# Inputs1.net
KiCad netlist of a schematic drawn in Altium Designer
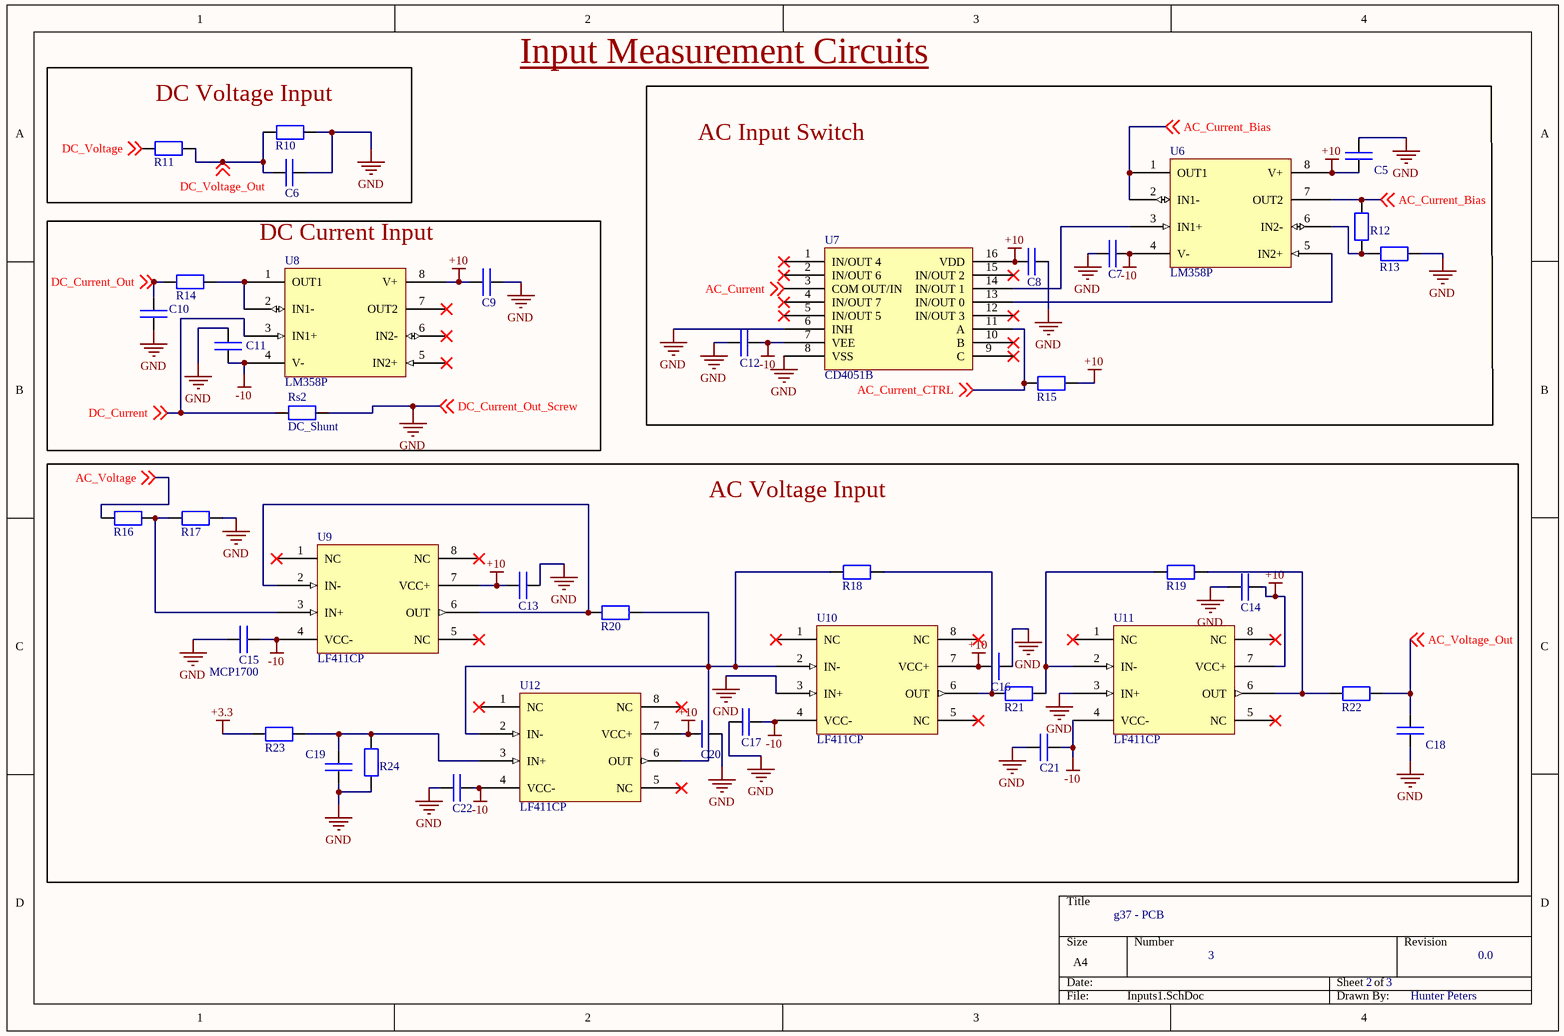
[diagram p0: Inputs1.SchDoc]

(export (version "E")
  (design (tool "Eeschema 10.0.6"))
  (components
    (comp (ref "C5")
      (value "Capacitor")
      (footprint "Capacitor")
      (libsource (lib "Schlib1") (part "Capacitor"))
    )
    (comp (ref "C6")
      (value "Capacitor")
      (footprint "Capacitor")
      (libsource (lib "Schlib1") (part "Capacitor"))
    )
    (comp (ref "C7")
      (value "Capacitor")
      (footprint "Capacitor")
      (libsource (lib "Schlib1") (part "Capacitor"))
    )
    (comp (ref "C8")
      (value "Capacitor")
      (footprint "Capacitor")
      (libsource (lib "Schlib1") (part "Capacitor"))
    )
    (comp (ref "C9")
      (value "Capacitor")
      (footprint "Capacitor")
      (libsource (lib "Schlib1") (part "Capacitor"))
    )
    (comp (ref "C10")
      (value "Capacitor")
      (footprint "Capacitor")
      (libsource (lib "Schlib1") (part "Capacitor"))
    )
    (comp (ref "C11")
      (value "Capacitor")
      (footprint "Capacitor")
      (libsource (lib "Schlib1") (part "Capacitor"))
    )
    (comp (ref "C12")
      (value "Capacitor")
      (footprint "Capacitor")
      (libsource (lib "Schlib1") (part "Capacitor"))
    )
    (comp (ref "C13")
      (value "Capacitor")
      (footprint "Capacitor")
      (libsource (lib "Schlib1") (part "Capacitor"))
    )
    (comp (ref "C14")
      (value "Capacitor")
      (footprint "Capacitor")
      (libsource (lib "Schlib1") (part "Capacitor"))
    )
    (comp (ref "C15")
      (value "Capacitor")
      (footprint "Capacitor")
      (libsource (lib "Schlib1") (part "Capacitor"))
    )
    (comp (ref "C16")
      (value "Capacitor")
      (footprint "Capacitor")
      (libsource (lib "Schlib1") (part "Capacitor"))
    )
    (comp (ref "C17")
      (value "Capacitor")
      (footprint "Capacitor")
      (libsource (lib "Schlib1") (part "Capacitor"))
    )
    (comp (ref "C18")
      (value "Capacitor")
      (footprint "Capacitor")
      (libsource (lib "Schlib1") (part "Capacitor"))
    )
    (comp (ref "C19")
      (value "Capacitor")
      (footprint "Capacitor")
      (libsource (lib "Schlib1") (part "Capacitor"))
    )
    (comp (ref "C20")
      (value "Capacitor")
      (footprint "Capacitor")
      (libsource (lib "Schlib1") (part "Capacitor"))
    )
    (comp (ref "C21")
      (value "Capacitor")
      (footprint "Capacitor")
      (libsource (lib "Schlib1") (part "Capacitor"))
    )
    (comp (ref "C22")
      (value "Capacitor")
      (footprint "Capacitor")
      (libsource (lib "Schlib1") (part "Capacitor"))
    )
    (comp (ref "R10") (value "Resistor") (footprint "Resistor") (libsource (lib "Schlib1") (part "Resistor")))
    (comp (ref "R11") (value "Resistor") (footprint "Resistor") (libsource (lib "Schlib1") (part "Resistor")))
    (comp (ref "R12") (value "Resistor") (footprint "Resistor") (libsource (lib "Schlib1") (part "Resistor")))
    (comp (ref "R13") (value "Resistor") (footprint "Resistor") (libsource (lib "Schlib1") (part "Resistor")))
    (comp (ref "R14") (value "Resistor") (footprint "Resistor") (libsource (lib "Schlib1") (part "Resistor")))
    (comp (ref "R15") (value "4.7kΩ") (footprint "Resistor") (libsource (lib "Schlib1") (part "Resistor")))
    (comp (ref "R16") (value "Resistor") (footprint "Resistor") (libsource (lib "Schlib1") (part "Resistor")))
    (comp (ref "R17") (value "Resistor") (footprint "Resistor") (libsource (lib "Schlib1") (part "Resistor")))
    (comp (ref "R18") (value "Resistor") (footprint "Resistor") (libsource (lib "Schlib1") (part "Resistor")))
    (comp (ref "R19") (value "Resistor") (footprint "Resistor") (libsource (lib "Schlib1") (part "Resistor")))
    (comp (ref "R20") (value "Resistor") (footprint "Resistor") (libsource (lib "Schlib1") (part "Resistor")))
    (comp (ref "R21") (value "Resistor") (footprint "Resistor") (libsource (lib "Schlib1") (part "Resistor")))
    (comp (ref "R22") (value "Resistor") (footprint "Resistor") (libsource (lib "Schlib1") (part "Resistor")))
    (comp (ref "R23") (value "Resistor") (footprint "Resistor") (libsource (lib "Schlib1") (part "Resistor")))
    (comp (ref "R24") (value "Resistor") (footprint "Resistor") (libsource (lib "Schlib1") (part "Resistor")))
    (comp (ref "Rs2") (value "DC_Shunt") (footprint "DC_Shunt") (libsource (lib "Schlib1") (part "DC_Shunt")))
    (comp (ref "U6")
      (value "LM358P")
      (footprint "Op Amp")
      (description "Operational Amplifier, Dual, 700 Khz, 2, 0.4 V/ S, 1.5V To 16V, Dip, 8 Rohs Compliant: Yes")
      (fields (field (name "MANUFACTURER") "Texas Instruments"))
      (libsource (lib "Schlib1") (part "LM358P"))
    )
    (comp (ref "U7")
      (value "CD4051B")
      (footprint "Multiplexor")
      (description "CD4051B Series 20 V 100 nA CMOS Single 8-Channel Analog Multiplexer - PDIP-16")
      (fields
        (field (name "MANUFACTURER") "Texas Instruments")
        (field (name "MANUFACTURER PART NUMBER") "CD4051BE")
      )
      (libsource (lib "Schlib1") (part "CD4051BE"))
    )
    (comp (ref "U8")
      (value "LM358P")
      (footprint "Op Amp")
      (description "Operational Amplifier, Dual, 700 Khz, 2, 0.4 V/ S, 1.5V To 16V, Dip, 8 Rohs Compliant: Yes")
      (fields (field (name "MANUFACTURER") "Texas Instruments"))
      (libsource (lib "Schlib1") (part "LM358P"))
    )
    (comp (ref "U9")
      (value "LF411CP")
      (footprint "Op Amp")
      (description "Operational Amplifier, 1 Func, 2000uV Offset-Max, JFET, PDIP8")
      (fields (field (name "MANUFACTURER") "Texas Instruments"))
      (libsource (lib "Schlib1") (part "LF411CP"))
    )
    (comp (ref "U10")
      (value "LF411CP")
      (footprint "Op Amp")
      (description "Operational Amplifier, 1 Func, 2000uV Offset-Max, JFET, PDIP8")
      (fields (field (name "MANUFACTURER") "Texas Instruments"))
      (libsource (lib "Schlib1") (part "LF411CP"))
    )
    (comp (ref "U11")
      (value "LF411CP")
      (footprint "Op Amp")
      (description "Operational Amplifier, 1 Func, 2000uV Offset-Max, JFET, PDIP8")
      (fields (field (name "MANUFACTURER") "Texas Instruments"))
      (libsource (lib "Schlib1") (part "LF411CP"))
    )
    (comp (ref "U12")
      (value "LF411CP")
      (footprint "Op Amp")
      (description "Operational Amplifier, 1 Func, 2000uV Offset-Max, JFET, PDIP8")
      (fields (field (name "MANUFACTURER") "Texas Instruments"))
      (libsource (lib "Schlib1") (part "LF411CP"))
    )
  )
  (nets
    (net (code "1") (name "+3.3") (class "Default")
      (node (ref "R23") (pin "1") (pinfunction "1_1") (pintype "passive"))
    )
    (net (code "2") (name "+10") (class "Default")
      (node (ref "C13") (pin "1") (pinfunction "1_1") (pintype "passive"))
      (node (ref "C14") (pin "1") (pinfunction "1_1") (pintype "passive"))
      (node (ref "C16") (pin "1") (pinfunction "1_1") (pintype "passive"))
      (node (ref "C20") (pin "1") (pinfunction "1_1") (pintype "passive"))
      (node (ref "C5") (pin "1") (pinfunction "1_1") (pintype "passive"))
      (node (ref "C8") (pin "1") (pinfunction "1_1") (pintype "passive"))
      (node (ref "C9") (pin "1") (pinfunction "1_1") (pintype "passive"))
      (node (ref "R15") (pin "2") (pinfunction "2_2") (pintype "passive"))
      (node (ref "U10") (pin "7") (pinfunction "VCC+_7") (pintype "power_in"))
      (node (ref "U11") (pin "7") (pinfunction "VCC+_7") (pintype "power_in"))
      (node (ref "U12") (pin "7") (pinfunction "VCC+_7") (pintype "power_in"))
      (node (ref "U6") (pin "8") (pinfunction "V+_8") (pintype "passive"))
      (node (ref "U7") (pin "16") (pinfunction "VDD_16") (pintype "passive"))
      (node (ref "U8") (pin "8") (pinfunction "V+_8") (pintype "passive"))
      (node (ref "U9") (pin "7") (pinfunction "VCC+_7") (pintype "power_in"))
    )
    (net (code "3") (name "-10") (class "Default")
      (node (ref "C11") (pin "1") (pinfunction "1_1") (pintype "passive"))
      (node (ref "C12") (pin "2") (pinfunction "2_2") (pintype "passive"))
      (node (ref "C15") (pin "2") (pinfunction "2_2") (pintype "passive"))
      (node (ref "C17") (pin "2") (pinfunction "2_2") (pintype "passive"))
      (node (ref "C21") (pin "2") (pinfunction "2_2") (pintype "passive"))
      (node (ref "C22") (pin "2") (pinfunction "2_2") (pintype "passive"))
      (node (ref "C7") (pin "2") (pinfunction "2_2") (pintype "passive"))
      (node (ref "U10") (pin "4") (pinfunction "VCC-_4") (pintype "power_in"))
      (node (ref "U11") (pin "4") (pinfunction "VCC-_4") (pintype "power_in"))
      (node (ref "U12") (pin "4") (pinfunction "VCC-_4") (pintype "power_in"))
      (node (ref "U6") (pin "4") (pinfunction "V-_4") (pintype "power_in"))
      (node (ref "U7") (pin "7") (pinfunction "VEE_7") (pintype "passive"))
      (node (ref "U8") (pin "4") (pinfunction "V-_4") (pintype "power_in"))
      (node (ref "U9") (pin "4") (pinfunction "VCC-_4") (pintype "power_in"))
    )
    (net (code "4") (name "AC_Current") (class "Default")
      (node (ref "U7") (pin "3") (pinfunction "COM_OUT/IN_3") (pintype "passive"))
    )
    (net (code "5") (name "AC_Current_Bias") (class "Default")
      (node (ref "R12") (pin "2") (pinfunction "2_2") (pintype "passive"))
      (node (ref "U6") (pin "1") (pinfunction "OUT1_1") (pintype "passive"))
      (node (ref "U6") (pin "2") (pinfunction "IN1-_2") (pintype "bidirectional"))
      (node (ref "U6") (pin "7") (pinfunction "OUT2_7") (pintype "passive"))
    )
    (net (code "6") (name "AC_Current_CTRL") (class "Default")
      (node (ref "R15") (pin "1") (pinfunction "1_1") (pintype "passive"))
      (node (ref "U7") (pin "11") (pinfunction "A_11") (pintype "passive"))
    )
    (net (code "7") (name "AC_Voltage") (class "Default")
      (node (ref "R16") (pin "1") (pinfunction "1_1") (pintype "passive"))
    )
    (net (code "8") (name "AC_Voltage_Out") (class "Default")
      (node (ref "C18") (pin "2") (pinfunction "2_2") (pintype "passive"))
      (node (ref "R22") (pin "2") (pinfunction "2_2") (pintype "passive"))
    )
    (net (code "9") (name "DC_Current") (class "Default")
      (node (ref "Rs2") (pin "1") (pinfunction "1_1") (pintype "passive"))
      (node (ref "U8") (pin "3") (pinfunction "IN1+_3") (pintype "input"))
    )
    (net (code "10") (name "DC_Current_Out") (class "Default")
      (node (ref "C10") (pin "2") (pinfunction "2_2") (pintype "passive"))
      (node (ref "R14") (pin "1") (pinfunction "1_1") (pintype "passive"))
    )
    (net (code "11") (name "DC_Current_Out_Screw") (class "Default")
      (node (ref "C10") (pin "1") (pinfunction "1_1") (pintype "passive"))
      (node (ref "C11") (pin "2") (pinfunction "2_2") (pintype "passive"))
      (node (ref "C12") (pin "1") (pinfunction "1_1") (pintype "passive"))
      (node (ref "C13") (pin "2") (pinfunction "2_2") (pintype "passive"))
      (node (ref "C14") (pin "2") (pinfunction "2_2") (pintype "passive"))
      (node (ref "C15") (pin "1") (pinfunction "1_1") (pintype "passive"))
      (node (ref "C16") (pin "2") (pinfunction "2_2") (pintype "passive"))
      (node (ref "C17") (pin "1") (pinfunction "1_1") (pintype "passive"))
      (node (ref "C18") (pin "1") (pinfunction "1_1") (pintype "passive"))
      (node (ref "C19") (pin "1") (pinfunction "1_1") (pintype "passive"))
      (node (ref "C20") (pin "2") (pinfunction "2_2") (pintype "passive"))
      (node (ref "C21") (pin "1") (pinfunction "1_1") (pintype "passive"))
      (node (ref "C22") (pin "1") (pinfunction "1_1") (pintype "passive"))
      (node (ref "C5") (pin "2") (pinfunction "2_2") (pintype "passive"))
      (node (ref "C6") (pin "2") (pinfunction "2_2") (pintype "passive"))
      (node (ref "C7") (pin "1") (pinfunction "1_1") (pintype "passive"))
      (node (ref "C8") (pin "2") (pinfunction "2_2") (pintype "passive"))
      (node (ref "C9") (pin "2") (pinfunction "2_2") (pintype "passive"))
      (node (ref "R10") (pin "2") (pinfunction "2_2") (pintype "passive"))
      (node (ref "R13") (pin "1") (pinfunction "1_1") (pintype "passive"))
      (node (ref "R17") (pin "2") (pinfunction "2_2") (pintype "passive"))
      (node (ref "R24") (pin "1") (pinfunction "1_1") (pintype "passive"))
      (node (ref "Rs2") (pin "2") (pinfunction "2_2") (pintype "passive"))
      (node (ref "U10") (pin "3") (pinfunction "IN+_3") (pintype "input"))
      (node (ref "U11") (pin "3") (pinfunction "IN+_3") (pintype "input"))
      (node (ref "U7") (pin "6") (pinfunction "INH_6") (pintype "passive"))
      (node (ref "U7") (pin "8") (pinfunction "VSS_8") (pintype "passive"))
    )
    (net (code "12") (name "DC_Voltage") (class "Default")
      (node (ref "R11") (pin "2") (pinfunction "2_2") (pintype "passive"))
    )
    (net (code "13") (name "DC_Voltage_Out") (class "Default")
      (node (ref "C6") (pin "1") (pinfunction "1_1") (pintype "passive"))
      (node (ref "R10") (pin "1") (pinfunction "1_1") (pintype "passive"))
      (node (ref "R11") (pin "1") (pinfunction "1_1") (pintype "passive"))
    )
    (net (code "14") (name "Net-(U6-IN1+)") (class "Default")
      (node (ref "U6") (pin "3") (pinfunction "IN1+_3") (pintype "input"))
      (node (ref "U7") (pin "14") (pinfunction "IN/OUT_1_14") (pintype "passive"))
    )
    (net (code "15") (name "Net-(U6-IN2+)") (class "Default")
      (node (ref "U6") (pin "5") (pinfunction "IN2+_5") (pintype "input"))
      (node (ref "U7") (pin "13") (pinfunction "IN/OUT_0_13") (pintype "passive"))
    )
    (net (code "16") (name "Net-(U6-IN2-)") (class "Default")
      (node (ref "R12") (pin "1") (pinfunction "1_1") (pintype "passive"))
      (node (ref "R13") (pin "2") (pinfunction "2_2") (pintype "passive"))
      (node (ref "U6") (pin "6") (pinfunction "IN2-_6") (pintype "bidirectional"))
    )
    (net (code "17") (name "Net-(U8-IN1-)") (class "Default")
      (node (ref "R14") (pin "2") (pinfunction "2_2") (pintype "passive"))
      (node (ref "U8") (pin "1") (pinfunction "OUT1_1") (pintype "passive"))
      (node (ref "U8") (pin "2") (pinfunction "IN1-_2") (pintype "bidirectional"))
    )
    (net (code "18") (name "Net-(U9-IN+)") (class "Default")
      (node (ref "R16") (pin "2") (pinfunction "2_2") (pintype "passive"))
      (node (ref "R17") (pin "1") (pinfunction "1_1") (pintype "passive"))
      (node (ref "U9") (pin "3") (pinfunction "IN+_3") (pintype "input"))
    )
    (net (code "19") (name "Net-(U9-IN-)") (class "Default")
      (node (ref "R20") (pin "1") (pinfunction "1_1") (pintype "passive"))
      (node (ref "U9") (pin "2") (pinfunction "IN-_2") (pintype "input"))
      (node (ref "U9") (pin "6") (pinfunction "OUT_6") (pintype "output"))
    )
    (net (code "20") (name "Net-(U10-IN-)") (class "Default")
      (node (ref "R18") (pin "1") (pinfunction "1_1") (pintype "passive"))
      (node (ref "R20") (pin "2") (pinfunction "2_2") (pintype "passive"))
      (node (ref "U10") (pin "2") (pinfunction "IN-_2") (pintype "input"))
      (node (ref "U12") (pin "2") (pinfunction "IN-_2") (pintype "input"))
      (node (ref "U12") (pin "6") (pinfunction "OUT_6") (pintype "output"))
    )
    (net (code "21") (name "Net-(U10-OUT)") (class "Default")
      (node (ref "R18") (pin "2") (pinfunction "2_2") (pintype "passive"))
      (node (ref "R21") (pin "1") (pinfunction "1_1") (pintype "passive"))
      (node (ref "U10") (pin "6") (pinfunction "OUT_6") (pintype "output"))
    )
    (net (code "22") (name "Net-(U11-IN-)") (class "Default")
      (node (ref "R19") (pin "1") (pinfunction "1_1") (pintype "passive"))
      (node (ref "R21") (pin "2") (pinfunction "2_2") (pintype "passive"))
      (node (ref "U11") (pin "2") (pinfunction "IN-_2") (pintype "input"))
    )
    (net (code "23") (name "Net-(U11-OUT)") (class "Default")
      (node (ref "R19") (pin "2") (pinfunction "2_2") (pintype "passive"))
      (node (ref "R22") (pin "1") (pinfunction "1_1") (pintype "passive"))
      (node (ref "U11") (pin "6") (pinfunction "OUT_6") (pintype "output"))
    )
    (net (code "24") (name "Net-(U12-IN+)") (class "Default")
      (node (ref "C19") (pin "2") (pinfunction "2_2") (pintype "passive"))
      (node (ref "R23") (pin "2") (pinfunction "2_2") (pintype "passive"))
      (node (ref "R24") (pin "2") (pinfunction "2_2") (pintype "passive"))
      (node (ref "U12") (pin "3") (pinfunction "IN+_3") (pintype "input"))
    )
    (net (code "25") (name "unconnected-(U7-B-Pad10)") (class "Default")
      (node (ref "U7") (pin "10") (pinfunction "B_10") (pintype "passive+no_connect"))
    )
    (net (code "26") (name "unconnected-(U7-C-Pad9)") (class "Default")
      (node (ref "U7") (pin "9") (pinfunction "C_9") (pintype "passive+no_connect"))
    )
    (net (code "27") (name "unconnected-(U7-IN{slash}OUT_2-Pad15)") (class "Default")
      (node (ref "U7") (pin "15") (pinfunction "IN/OUT_2_15") (pintype "passive+no_connect"))
    )
    (net (code "28") (name "unconnected-(U7-IN{slash}OUT_3-Pad12)") (class "Default")
      (node (ref "U7") (pin "12") (pinfunction "IN/OUT_3_12") (pintype "passive+no_connect"))
    )
    (net (code "29") (name "unconnected-(U7-IN{slash}OUT_4-Pad1)") (class "Default")
      (node (ref "U7") (pin "1") (pinfunction "IN/OUT_4_1") (pintype "passive+no_connect"))
    )
    (net (code "30") (name "unconnected-(U7-IN{slash}OUT_5-Pad5)") (class "Default")
      (node (ref "U7") (pin "5") (pinfunction "IN/OUT_5_5") (pintype "passive+no_connect"))
    )
    (net (code "31") (name "unconnected-(U7-IN{slash}OUT_6-Pad2)") (class "Default")
      (node (ref "U7") (pin "2") (pinfunction "IN/OUT_6_2") (pintype "passive+no_connect"))
    )
    (net (code "32") (name "unconnected-(U7-IN{slash}OUT_7-Pad4)") (class "Default")
      (node (ref "U7") (pin "4") (pinfunction "IN/OUT_7_4") (pintype "passive+no_connect"))
    )
    (net (code "33") (name "unconnected-(U8-IN2+-Pad5)") (class "Default")
      (node (ref "U8") (pin "5") (pinfunction "IN2+_5") (pintype "input+no_connect"))
    )
    (net (code "34") (name "unconnected-(U8-IN2--Pad6)") (class "Default")
      (node (ref "U8") (pin "6") (pinfunction "IN2-_6") (pintype "bidirectional+no_connect"))
    )
    (net (code "35") (name "unconnected-(U8-OUT2-Pad7)") (class "Default")
      (node (ref "U8") (pin "7") (pinfunction "OUT2_7") (pintype "passive+no_connect"))
    )
    (net (code "36") (name "unconnected-(U9-NC-Pad1)") (class "Default")
      (node (ref "U9") (pin "1") (pinfunction "NC_1") (pintype "passive+no_connect"))
    )
    (net (code "37") (name "unconnected-(U9-NC-Pad5)") (class "Default")
      (node (ref "U9") (pin "5") (pinfunction "NC_5") (pintype "passive+no_connect"))
    )
    (net (code "38") (name "unconnected-(U9-NC-Pad8)") (class "Default")
      (node (ref "U9") (pin "8") (pinfunction "NC_8") (pintype "passive+no_connect"))
    )
    (net (code "39") (name "unconnected-(U10-NC-Pad1)") (class "Default")
      (node (ref "U10") (pin "1") (pinfunction "NC_1") (pintype "passive+no_connect"))
    )
    (net (code "40") (name "unconnected-(U10-NC-Pad5)") (class "Default")
      (node (ref "U10") (pin "5") (pinfunction "NC_5") (pintype "passive+no_connect"))
    )
    (net (code "41") (name "unconnected-(U10-NC-Pad8)") (class "Default")
      (node (ref "U10") (pin "8") (pinfunction "NC_8") (pintype "passive+no_connect"))
    )
    (net (code "42") (name "unconnected-(U11-NC-Pad1)") (class "Default")
      (node (ref "U11") (pin "1") (pinfunction "NC_1") (pintype "passive+no_connect"))
    )
    (net (code "43") (name "unconnected-(U11-NC-Pad5)") (class "Default")
      (node (ref "U11") (pin "5") (pinfunction "NC_5") (pintype "passive+no_connect"))
    )
    (net (code "44") (name "unconnected-(U11-NC-Pad8)") (class "Default")
      (node (ref "U11") (pin "8") (pinfunction "NC_8") (pintype "passive+no_connect"))
    )
    (net (code "45") (name "unconnected-(U12-NC-Pad1)") (class "Default")
      (node (ref "U12") (pin "1") (pinfunction "NC_1") (pintype "passive+no_connect"))
    )
    (net (code "46") (name "unconnected-(U12-NC-Pad5)") (class "Default")
      (node (ref "U12") (pin "5") (pinfunction "NC_5") (pintype "passive+no_connect"))
    )
    (net (code "47") (name "unconnected-(U12-NC-Pad8)") (class "Default")
      (node (ref "U12") (pin "8") (pinfunction "NC_8") (pintype "passive+no_connect"))
    )
  )
)
